# BOTCPCB.net
KiCad netlist of a schematic drawn in EAGLE
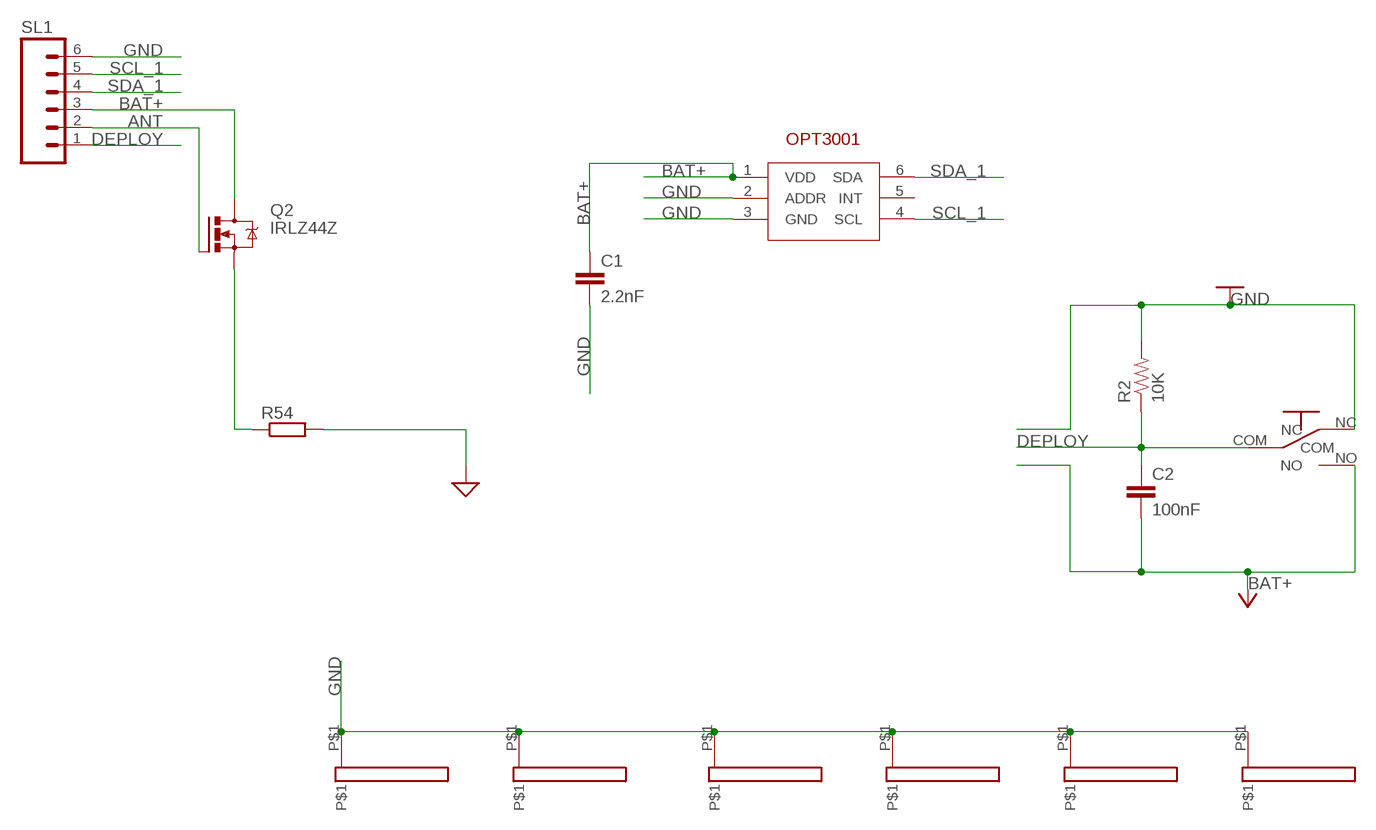
[diagram p0: schematic, sheet 1]

(export (version "E")
  (design (tool "Eeschema 10.0.6"))
  (components
    (comp (ref "C1")
      (value "2.2nF")
      (footprint "eagle-import:0603")
      (libsource (lib "eagle-import") (part "2.2NF/2200PF-0603-50V-10%"))
    )
    (comp (ref "C2")
      (value "100nF")
      (footprint "eagle-import:0805")
      (libsource (lib "eagle-import") (part "CAP0805"))
    )
    (comp (ref "Q2")
      (value "IRLZ44Z")
      (footprint "eagle-import:TO220BH")
      (libsource (lib "eagle-import") (part "IRLZ44Z"))
    )
    (comp (ref "R2")
      (value "10K")
      (footprint "eagle-import:0805")
      (libsource (lib "eagle-import") (part "RESISTOR"))
    )
    (comp (ref "R54")
      (value "R-EU_0204/2V")
      (footprint "eagle-import:0204V")
      (libsource (lib "eagle-import") (part "R-EU_0204/2V"))
    )
    (comp (ref "SL1")
      (value "M06")
      (footprint "eagle-import:06P")
      (libsource (lib "eagle-import") (part "M06"))
    )
    (comp (ref "U$1")
      (value "16X2")
      (footprint "eagle-import:16X2")
      (libsource (lib "eagle-import") (part "16X2"))
    )
    (comp (ref "U$2")
      (value "16X2")
      (footprint "eagle-import:16X2")
      (libsource (lib "eagle-import") (part "16X2"))
    )
    (comp (ref "U$4")
      (value "16X2")
      (footprint "eagle-import:16X2")
      (libsource (lib "eagle-import") (part "16X2"))
    )
    (comp (ref "U$5")
      (value "16X2")
      (footprint "eagle-import:16X2")
      (libsource (lib "eagle-import") (part "16X2"))
    )
    (comp (ref "U$6")
      (value "OMRON-D2FA")
      (footprint "eagle-import:OMRON-D2F-A")
      (libsource (lib "eagle-import") (part "OMRON-D2FA"))
    )
    (comp (ref "U$7")
      (value "16X2")
      (footprint "eagle-import:16X2")
      (libsource (lib "eagle-import") (part "16X2"))
    )
    (comp (ref "U$8")
      (value "16X2")
      (footprint "eagle-import:16X2")
      (libsource (lib "eagle-import") (part "16X2"))
    )
    (comp (ref "U1")
      (value "SON65P200X200X65-7N")
      (footprint "eagle-import:SON65P200X200X65-7N")
      (fields (field (name "MANUFACTURER") "Maxim Integrated"))
      (libsource (lib "eagle-import") (part "SON65P200X200X65-7N"))
    )
  )
  (nets
    (net (code "1") (name "/ANT") (class "Default")
      (node (ref "Q2") (pin "G") (pinfunction "G_G") (pintype "passive"))
      (node (ref "SL1") (pin "2") (pinfunction "2_2") (pintype "passive"))
    )
    (net (code "2") (name "/DEPLOY") (class "Default")
      (node (ref "C2") (pin "1") (pinfunction "1_1") (pintype "passive"))
      (node (ref "R2") (pin "1") (pinfunction "1_1") (pintype "passive"))
      (node (ref "SL1") (pin "1") (pinfunction "1_1") (pintype "passive"))
      (node (ref "U$6") (pin "COM") (pinfunction "COM_COM") (pintype "bidirectional"))
    )
    (net (code "3") (name "/SCL_1") (class "Default")
      (node (ref "SL1") (pin "5") (pinfunction "5_5") (pintype "passive"))
      (node (ref "U1") (pin "4") (pinfunction "SCL_4") (pintype "bidirectional"))
    )
    (net (code "4") (name "/SDA_1") (class "Default")
      (node (ref "SL1") (pin "4") (pinfunction "4_4") (pintype "passive"))
      (node (ref "U1") (pin "6") (pinfunction "SDA_6") (pintype "bidirectional"))
    )
    (net (code "5") (name "GND") (class "Default")
      (node (ref "C1") (pin "2") (pinfunction "2_2") (pintype "passive"))
      (node (ref "R2") (pin "2") (pinfunction "2_2") (pintype "passive"))
      (node (ref "R54") (pin "2") (pinfunction "2_2") (pintype "passive"))
      (node (ref "SL1") (pin "6") (pinfunction "6_6") (pintype "passive"))
      (node (ref "U$1") (pin "P$1") (pinfunction "P$1_P$1") (pintype "bidirectional"))
      (node (ref "U$2") (pin "P$1") (pinfunction "P$1_P$1") (pintype "bidirectional"))
      (node (ref "U$4") (pin "P$1") (pinfunction "P$1_P$1") (pintype "bidirectional"))
      (node (ref "U$5") (pin "P$1") (pinfunction "P$1_P$1") (pintype "bidirectional"))
      (node (ref "U$6") (pin "NC") (pinfunction "NC_NC") (pintype "bidirectional"))
      (node (ref "U$7") (pin "P$1") (pinfunction "P$1_P$1") (pintype "bidirectional"))
      (node (ref "U$8") (pin "P$1") (pinfunction "P$1_P$1") (pintype "bidirectional"))
      (node (ref "U1") (pin "2") (pinfunction "ADDR_2") (pintype "bidirectional"))
      (node (ref "U1") (pin "3") (pinfunction "GND_3") (pintype "bidirectional"))
    )
    (net (code "6") (name "Net-(Q2-PadS)") (class "Default")
      (node (ref "Q2") (pin "S") (pinfunction "S_S") (pintype "passive"))
      (node (ref "R54") (pin "1") (pinfunction "1_1") (pintype "passive"))
    )
    (net (code "7") (name "VCC") (class "Default")
      (node (ref "C1") (pin "1") (pinfunction "1_1") (pintype "passive"))
      (node (ref "C2") (pin "2") (pinfunction "2_2") (pintype "passive"))
      (node (ref "Q2") (pin "D") (pinfunction "D_D") (pintype "passive"))
      (node (ref "SL1") (pin "3") (pinfunction "3_3") (pintype "passive"))
      (node (ref "U$6") (pin "NO") (pinfunction "NO_NO") (pintype "bidirectional"))
      (node (ref "U1") (pin "1") (pinfunction "VDD_1") (pintype "bidirectional"))
    )
    (net (code "8") (name "unconnected-(U1-INT-Pad5)") (class "Default")
      (node (ref "U1") (pin "5") (pinfunction "INT_5") (pintype "bidirectional"))
    )
  )
)
